# GPRS_0831.net
KiCad netlist of a schematic drawn in Altium Designer
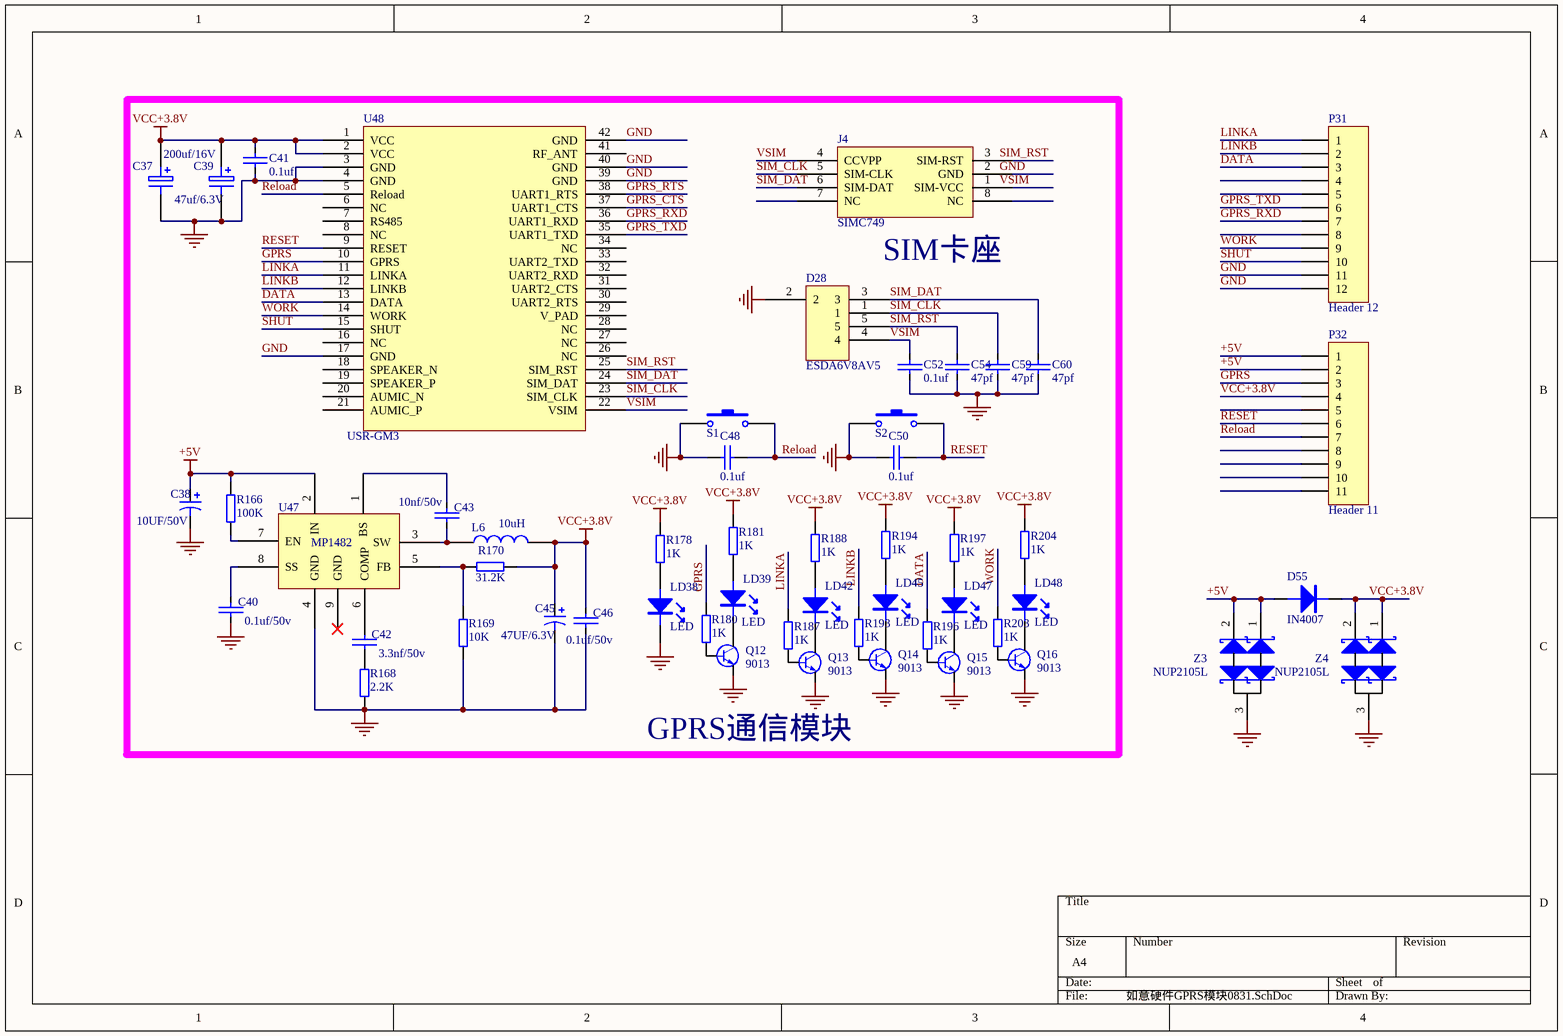
[diagram p0: 如意硬件GPRS模块0831.SchDoc]

(export (version "E")
  (design (tool "Eeschema 10.0.6"))
  (components
    (comp (ref "C37")
      (value "200uf/16V")
      (footprint "1206D-S")
      (description "Electrolytic Capacitor")
      (libsource (lib "*") (part "ELECTRO1"))
    )
    (comp (ref "C38")
      (value "10UF/50V")
      (footprint "1206D-S")
      (description "Polarized Capacitor (Radial)")
      (fields (field (name "Comment") "Cap Pol1") (field (name "PUBLISHER") "Altium Limited"))
      (libsource (lib "Miscellaneous Devices") (part "Cap Pol1"))
    )
    (comp (ref "C39")
      (value "47uf/6.3V")
      (footprint "1206D-S")
      (description "Electrolytic Capacitor")
      (libsource (lib "*") (part "ELECTRO1"))
    )
    (comp (ref "C40") (value "0.1uf/50v") (footprint "0603C-1") (libsource (lib "*") (part "C")))
    (comp (ref "C41") (value "0.1uf") (footprint "0603C-1") (libsource (lib "*") (part "C")))
    (comp (ref "C42") (value "3.3nf/50v") (footprint "0603C-1") (libsource (lib "*") (part "C")))
    (comp (ref "C43") (value "10nf/50v") (footprint "1206D-S") (libsource (lib "*") (part "C")))
    (comp (ref "C45")
      (value "47UF/6.3V")
      (footprint "1206D-S")
      (description "Polarized Capacitor (Radial)")
      (fields (field (name "Comment") "Cap Pol1") (field (name "PUBLISHER") "Altium Limited"))
      (libsource (lib "Miscellaneous Devices") (part "Cap Pol1"))
    )
    (comp (ref "C46") (value "0.1uf/50v") (footprint "0603C-1") (libsource (lib "*") (part "C")))
    (comp (ref "C48")
      (value "0.1uf")
      (footprint "0603C-1")
      (description "Capacitor")
      (libsource (lib "*") (part "CAP"))
    )
    (comp (ref "C50")
      (value "0.1uf")
      (footprint "0603C-1")
      (description "Capacitor")
      (libsource (lib "*") (part "CAP"))
    )
    (comp (ref "C52") (value "0.1uf") (footprint "0603C-1") (libsource (lib "*") (part "C")))
    (comp (ref "C54") (value "47pf") (footprint "0603C-1") (libsource (lib "*") (part "C")))
    (comp (ref "C59") (value "47pf") (footprint "0603C-1") (libsource (lib "*") (part "C")))
    (comp (ref "C60") (value "47pf") (footprint "0603C-1") (libsource (lib "*") (part "C")))
    (comp (ref "D28")
      (value "ESDA6V8AV5")
      (footprint "SOT-553")
      (libsource (lib "zongruyi") (part "ESDA6V8AV5"))
    )
    (comp (ref "D55")
      (value "IN4007")
      (footprint "DIODETP-5")
      (description "Diode")
      (libsource (lib "*") (part "DIODE"))
    )
    (comp (ref "J4") (value "SIMC749") (footprint "SIMPUSH") (libsource (lib "zongruyi") (part "SIMC749")))
    (comp (ref "L6") (value "10uH") (footprint "NR8030") (libsource (lib "*") (part "INDUCTOR")))
    (comp (ref "LD38") (value "LED") (footprint "LED_Z1") (libsource (lib "*") (part "LED")))
    (comp (ref "LD39") (value "LED") (footprint "LED_Z1") (libsource (lib "*") (part "LED")))
    (comp (ref "LD42") (value "LED") (footprint "LED_Z1") (libsource (lib "*") (part "LED")))
    (comp (ref "LD45") (value "LED") (footprint "LED_Z1") (libsource (lib "*") (part "LED")))
    (comp (ref "LD47") (value "LED") (footprint "LED_Z1") (libsource (lib "*") (part "LED")))
    (comp (ref "LD48") (value "LED") (footprint "LED_Z1") (libsource (lib "*") (part "LED")))
    (comp (ref "P31")
      (value "Header 12")
      (footprint "HDR1X12")
      (description "Header, 12-Pin")
      (fields (field (name "PUBLISHER") "Altium Limited"))
      (libsource (lib "Miscellaneous Connectors") (part "Header 12"))
    )
    (comp (ref "P32")
      (value "Header 11")
      (footprint "HDR1X11")
      (description "Header, 11-Pin")
      (fields (field (name "PUBLISHER") "Altium Limited"))
      (libsource (lib "Miscellaneous Connectors") (part "Header 11"))
    )
    (comp (ref "Q12") (value "9013") (footprint "SOT23-BCE") (libsource (lib "*") (part "NPN")))
    (comp (ref "Q13") (value "9013") (footprint "SOT23-BCE") (libsource (lib "*") (part "NPN")))
    (comp (ref "Q14") (value "9013") (footprint "SOT23-BCE") (libsource (lib "*") (part "NPN")))
    (comp (ref "Q15") (value "9013") (footprint "SOT23-BCE") (libsource (lib "*") (part "NPN")))
    (comp (ref "Q16") (value "9013") (footprint "SOT23-BCE") (libsource (lib "*") (part "NPN")))
    (comp (ref "R166") (value "100K") (footprint "0603R-1") (libsource (lib "") (part "RES-2_1")))
    (comp (ref "R168") (value "2.2K") (footprint "0603R-1") (libsource (lib "") (part "RES-2_1")))
    (comp (ref "R169") (value "10K") (footprint "0603R-1") (libsource (lib "") (part "RES-2_1")))
    (comp (ref "R170") (value "31.2K") (footprint "0603R-1") (libsource (lib "") (part "RES-2_1")))
    (comp (ref "R178") (value "1K") (footprint "0603R-1") (libsource (lib "*") (part "RES-2")))
    (comp (ref "R180") (value "1K") (footprint "0603R-1") (libsource (lib "*") (part "RES-2")))
    (comp (ref "R181") (value "1K") (footprint "0603R-1") (libsource (lib "*") (part "RES-2")))
    (comp (ref "R187") (value "1K") (footprint "0603R-1") (libsource (lib "*") (part "RES-2")))
    (comp (ref "R188") (value "1K") (footprint "0603R-1") (libsource (lib "*") (part "RES-2")))
    (comp (ref "R193") (value "1K") (footprint "0603R-1") (libsource (lib "*") (part "RES-2")))
    (comp (ref "R194") (value "1K") (footprint "0603R-1") (libsource (lib "*") (part "RES-2")))
    (comp (ref "R196") (value "1K") (footprint "0603R-1") (libsource (lib "*") (part "RES-2")))
    (comp (ref "R197") (value "1K") (footprint "0603R-1") (libsource (lib "*") (part "RES-2")))
    (comp (ref "R203") (value "1K") (footprint "0603R-1") (libsource (lib "*") (part "RES-2")))
    (comp (ref "R204") (value "1K") (footprint "0603R-1") (libsource (lib "*") (part "RES-2")))
    (comp (ref "S1")
      (value "SW-PB")
      (footprint "SW_PB4_A1")
      (description "Switch")
      (fields (field (name "PUBLISHER") "Altium Limited"))
      (libsource (lib "*") (part "SW-PB"))
    )
    (comp (ref "S2")
      (value "SW-PB")
      (footprint "SW_PB4_A1")
      (description "Switch")
      (fields (field (name "PUBLISHER") "Altium Limited"))
      (libsource (lib "*") (part "SW-PB"))
    )
    (comp (ref "U47") (value "MP1482") (footprint "SO-8") (libsource (lib "zongruyi") (part "MP1482")))
    (comp (ref "U48") (value "USR-GM3") (footprint "USR-GM3") (libsource (lib "zongruyi") (part "USR-GM3")))
    (comp (ref "Z3")
      (value "NUP2105L")
      (footprint "SOT-23")
      (description "过压保护")
      (libsource (lib "Fszhang") (part "PESD1CAN"))
    )
    (comp (ref "Z4")
      (value "NUP2105L")
      (footprint "SOT-23")
      (description "过压保护")
      (libsource (lib "Fszhang") (part "PESD1CAN"))
    )
  )
  (nets
    (net (code "1") (name "+5V") (class "Default")
      (node (ref "C38") (pin "1") (pinfunction "1_1") (pintype "passive"))
      (node (ref "D55") (pin "1") (pinfunction "A_1") (pintype "passive"))
      (node (ref "P32") (pin "1") (pinfunction "1_1") (pintype "passive"))
      (node (ref "P32") (pin "2") (pinfunction "2_2") (pintype "passive"))
      (node (ref "R166") (pin "1") (pinfunction "1_1") (pintype "passive"))
      (node (ref "U47") (pin "2") (pinfunction "IN_2") (pintype "passive"))
      (node (ref "Z3") (pin "1") (pintype "passive"))
      (node (ref "Z3") (pin "2") (pintype "passive"))
    )
    (net (code "2") (name "/DATA") (class "Default")
      (node (ref "P31") (pin "3") (pinfunction "3_3") (pintype "passive"))
      (node (ref "R196") (pin "1") (pinfunction "1_1") (pintype "passive"))
      (node (ref "U48") (pin "13") (pinfunction "DATA_13") (pintype "passive"))
    )
    (net (code "3") (name "/GPRS") (class "Default")
      (node (ref "P32") (pin "3") (pinfunction "3_3") (pintype "passive"))
      (node (ref "R180") (pin "1") (pinfunction "1_1") (pintype "passive"))
      (node (ref "U48") (pin "10") (pinfunction "GPRS_10") (pintype "passive"))
    )
    (net (code "4") (name "/GPRS_CTS") (class "Default")
      (node (ref "U48") (pin "37") (pinfunction "UART1_CTS_37") (pintype "passive"))
    )
    (net (code "5") (name "/GPRS_RTS") (class "Default")
      (node (ref "U48") (pin "38") (pinfunction "UART1_RTS_38") (pintype "passive"))
    )
    (net (code "6") (name "/GPRS_RXD") (class "Default")
      (node (ref "P31") (pin "7") (pinfunction "7_7") (pintype "passive"))
      (node (ref "U48") (pin "36") (pinfunction "UART1_RXD_36") (pintype "passive"))
    )
    (net (code "7") (name "/GPRS_TXD") (class "Default")
      (node (ref "P31") (pin "6") (pinfunction "6_6") (pintype "passive"))
      (node (ref "U48") (pin "35") (pinfunction "UART1_TXD_35") (pintype "passive"))
    )
    (net (code "8") (name "/LINKA") (class "Default")
      (node (ref "P31") (pin "1") (pinfunction "1_1") (pintype "passive"))
      (node (ref "R187") (pin "1") (pinfunction "1_1") (pintype "passive"))
      (node (ref "U48") (pin "11") (pinfunction "LINKA_11") (pintype "passive"))
    )
    (net (code "9") (name "/LINKB") (class "Default")
      (node (ref "P31") (pin "2") (pinfunction "2_2") (pintype "passive"))
      (node (ref "R193") (pin "1") (pinfunction "1_1") (pintype "passive"))
      (node (ref "U48") (pin "12") (pinfunction "LINKB_12") (pintype "passive"))
    )
    (net (code "10") (name "/RESET") (class "Default")
      (node (ref "C50") (pin "1") (pinfunction "1_1") (pintype "passive"))
      (node (ref "P32") (pin "6") (pinfunction "6_6") (pintype "passive"))
      (node (ref "S2") (pin "2") (pinfunction "2_2") (pintype "passive"))
      (node (ref "U48") (pin "9") (pinfunction "RESET_9") (pintype "passive"))
    )
    (net (code "11") (name "/Reload") (class "Default")
      (node (ref "C48") (pin "1") (pinfunction "1_1") (pintype "passive"))
      (node (ref "P32") (pin "7") (pinfunction "7_7") (pintype "passive"))
      (node (ref "S1") (pin "2") (pinfunction "2_2") (pintype "passive"))
      (node (ref "U48") (pin "5") (pinfunction "Reload_5") (pintype "passive"))
    )
    (net (code "12") (name "/SHUT") (class "Default")
      (node (ref "P31") (pin "10") (pinfunction "10_10") (pintype "passive"))
      (node (ref "U48") (pin "15") (pinfunction "SHUT_15") (pintype "passive"))
    )
    (net (code "13") (name "/SIM_CLK") (class "Default")
      (node (ref "C59") (pin "1") (pinfunction "1_1") (pintype "passive"))
      (node (ref "D28") (pin "1") (pinfunction "1_1") (pintype "passive"))
      (node (ref "J4") (pin "5") (pinfunction "SIM-CLK_5") (pintype "passive"))
      (node (ref "U48") (pin "23") (pinfunction "SIM_CLK_23") (pintype "passive"))
    )
    (net (code "14") (name "/SIM_DAT") (class "Default")
      (node (ref "C60") (pin "1") (pinfunction "1_1") (pintype "passive"))
      (node (ref "D28") (pin "3") (pinfunction "3_3") (pintype "passive"))
      (node (ref "J4") (pin "6") (pinfunction "SIM-DAT_6") (pintype "passive"))
      (node (ref "U48") (pin "24") (pinfunction "SIM_DAT_24") (pintype "passive"))
    )
    (net (code "15") (name "/SIM_RST") (class "Default")
      (node (ref "C54") (pin "1") (pinfunction "1_1") (pintype "passive"))
      (node (ref "D28") (pin "5") (pinfunction "5_5") (pintype "passive"))
      (node (ref "U48") (pin "25") (pinfunction "SIM_RST_25") (pintype "passive"))
    )
    (net (code "16") (name "/VSIM") (class "Default")
      (node (ref "C52") (pin "1") (pinfunction "1_1") (pintype "passive"))
      (node (ref "D28") (pin "4") (pinfunction "4_4") (pintype "passive"))
      (node (ref "J4") (pin "4") (pinfunction "CCVPP_4") (pintype "passive"))
      (node (ref "U48") (pin "22") (pinfunction "VSIM_22") (pintype "passive"))
    )
    (net (code "17") (name "/WORK") (class "Default")
      (node (ref "P31") (pin "9") (pinfunction "9_9") (pintype "passive"))
      (node (ref "R203") (pin "1") (pinfunction "1_1") (pintype "passive"))
      (node (ref "U48") (pin "14") (pinfunction "WORK_14") (pintype "passive"))
    )
    (net (code "18") (name "GND") (class "Default")
      (node (ref "C37") (pin "2") (pinfunction "2_2") (pintype "passive"))
      (node (ref "C38") (pin "2") (pinfunction "2_2") (pintype "passive"))
      (node (ref "C39") (pin "2") (pinfunction "2_2") (pintype "passive"))
      (node (ref "C40") (pin "2") (pinfunction "2_2") (pintype "passive"))
      (node (ref "C41") (pin "2") (pinfunction "2_2") (pintype "passive"))
      (node (ref "C45") (pin "2") (pinfunction "2_2") (pintype "passive"))
      (node (ref "C46") (pin "2") (pinfunction "2_2") (pintype "passive"))
      (node (ref "C48") (pin "2") (pinfunction "2_2") (pintype "passive"))
      (node (ref "C50") (pin "2") (pinfunction "2_2") (pintype "passive"))
      (node (ref "C52") (pin "2") (pinfunction "2_2") (pintype "passive"))
      (node (ref "C54") (pin "2") (pinfunction "2_2") (pintype "passive"))
      (node (ref "C59") (pin "2") (pinfunction "2_2") (pintype "passive"))
      (node (ref "C60") (pin "2") (pinfunction "2_2") (pintype "passive"))
      (node (ref "D28") (pin "2") (pinfunction "2_2") (pintype "passive"))
      (node (ref "LD38") (pin "2") (pinfunction "2_2") (pintype "passive"))
      (node (ref "P31") (pin "11") (pinfunction "11_11") (pintype "passive"))
      (node (ref "P31") (pin "12") (pinfunction "12_12") (pintype "passive"))
      (node (ref "Q12") (pin "E") (pintype "passive"))
      (node (ref "Q13") (pin "E") (pintype "passive"))
      (node (ref "Q14") (pin "E") (pintype "passive"))
      (node (ref "Q15") (pin "E") (pintype "passive"))
      (node (ref "Q16") (pin "E") (pintype "passive"))
      (node (ref "R168") (pin "2") (pinfunction "2_2") (pintype "passive"))
      (node (ref "R169") (pin "2") (pinfunction "2_2") (pintype "passive"))
      (node (ref "S1") (pin "1") (pinfunction "1_1") (pintype "passive"))
      (node (ref "S2") (pin "1") (pinfunction "1_1") (pintype "passive"))
      (node (ref "U47") (pin "4") (pinfunction "GND_4") (pintype "passive"))
      (node (ref "U48") (pin "17") (pinfunction "GND_17") (pintype "passive"))
      (node (ref "U48") (pin "3") (pinfunction "GND_3") (pintype "passive"))
      (node (ref "U48") (pin "39") (pinfunction "GND_39") (pintype "passive"))
      (node (ref "U48") (pin "4") (pinfunction "GND_4") (pintype "passive"))
      (node (ref "U48") (pin "40") (pinfunction "GND_40") (pintype "passive"))
      (node (ref "U48") (pin "42") (pinfunction "GND_42") (pintype "passive"))
      (node (ref "Z3") (pin "3") (pintype "passive"))
      (node (ref "Z4") (pin "3") (pintype "passive"))
    )
    (net (code "19") (name "Net-(C42-Pad2)") (class "Default")
      (node (ref "C42") (pin "2") (pinfunction "2_2") (pintype "passive"))
      (node (ref "R168") (pin "1") (pinfunction "1_1") (pintype "passive"))
    )
    (net (code "20") (name "Net-(LD38-Pad1)") (class "Default")
      (node (ref "LD38") (pin "1") (pinfunction "1_1") (pintype "passive"))
      (node (ref "R178") (pin "2") (pinfunction "2_2") (pintype "passive"))
    )
    (net (code "21") (name "Net-(LD39-Pad1)") (class "Default")
      (node (ref "LD39") (pin "1") (pinfunction "1_1") (pintype "passive"))
      (node (ref "R181") (pin "2") (pinfunction "2_2") (pintype "passive"))
    )
    (net (code "22") (name "Net-(LD39-Pad2)") (class "Default")
      (node (ref "LD39") (pin "2") (pinfunction "2_2") (pintype "passive"))
      (node (ref "Q12") (pin "C") (pintype "passive"))
    )
    (net (code "23") (name "Net-(LD42-Pad1)") (class "Default")
      (node (ref "LD42") (pin "1") (pinfunction "1_1") (pintype "passive"))
      (node (ref "R188") (pin "2") (pinfunction "2_2") (pintype "passive"))
    )
    (net (code "24") (name "Net-(LD42-Pad2)") (class "Default")
      (node (ref "LD42") (pin "2") (pinfunction "2_2") (pintype "passive"))
      (node (ref "Q13") (pin "C") (pintype "passive"))
    )
    (net (code "25") (name "Net-(LD45-Pad1)") (class "Default")
      (node (ref "LD45") (pin "1") (pinfunction "1_1") (pintype "passive"))
      (node (ref "R194") (pin "2") (pinfunction "2_2") (pintype "passive"))
    )
    (net (code "26") (name "Net-(LD45-Pad2)") (class "Default")
      (node (ref "LD45") (pin "2") (pinfunction "2_2") (pintype "passive"))
      (node (ref "Q14") (pin "C") (pintype "passive"))
    )
    (net (code "27") (name "Net-(LD47-Pad1)") (class "Default")
      (node (ref "LD47") (pin "1") (pinfunction "1_1") (pintype "passive"))
      (node (ref "R197") (pin "2") (pinfunction "2_2") (pintype "passive"))
    )
    (net (code "28") (name "Net-(LD47-Pad2)") (class "Default")
      (node (ref "LD47") (pin "2") (pinfunction "2_2") (pintype "passive"))
      (node (ref "Q15") (pin "C") (pintype "passive"))
    )
    (net (code "29") (name "Net-(LD48-Pad1)") (class "Default")
      (node (ref "LD48") (pin "1") (pinfunction "1_1") (pintype "passive"))
      (node (ref "R204") (pin "2") (pinfunction "2_2") (pintype "passive"))
    )
    (net (code "30") (name "Net-(LD48-Pad2)") (class "Default")
      (node (ref "LD48") (pin "2") (pinfunction "2_2") (pintype "passive"))
      (node (ref "Q16") (pin "C") (pintype "passive"))
    )
    (net (code "31") (name "Net-(Q12-PadB)") (class "Default")
      (node (ref "Q12") (pin "B") (pintype "passive"))
      (node (ref "R180") (pin "2") (pinfunction "2_2") (pintype "passive"))
    )
    (net (code "32") (name "Net-(Q13-PadB)") (class "Default")
      (node (ref "Q13") (pin "B") (pintype "passive"))
      (node (ref "R187") (pin "2") (pinfunction "2_2") (pintype "passive"))
    )
    (net (code "33") (name "Net-(Q14-PadB)") (class "Default")
      (node (ref "Q14") (pin "B") (pintype "passive"))
      (node (ref "R193") (pin "2") (pinfunction "2_2") (pintype "passive"))
    )
    (net (code "34") (name "Net-(Q15-PadB)") (class "Default")
      (node (ref "Q15") (pin "B") (pintype "passive"))
      (node (ref "R196") (pin "2") (pinfunction "2_2") (pintype "passive"))
    )
    (net (code "35") (name "Net-(Q16-PadB)") (class "Default")
      (node (ref "Q16") (pin "B") (pintype "passive"))
      (node (ref "R203") (pin "2") (pinfunction "2_2") (pintype "passive"))
    )
    (net (code "36") (name "Net-(U47-BS)") (class "Default")
      (node (ref "C43") (pin "1") (pinfunction "1_1") (pintype "passive"))
      (node (ref "U47") (pin "1") (pinfunction "BS_1") (pintype "passive"))
    )
    (net (code "37") (name "Net-(U47-COMP)") (class "Default")
      (node (ref "C42") (pin "1") (pinfunction "1_1") (pintype "passive"))
      (node (ref "U47") (pin "6") (pinfunction "COMP_6") (pintype "passive"))
    )
    (net (code "38") (name "Net-(U47-EN)") (class "Default")
      (node (ref "R166") (pin "2") (pinfunction "2_2") (pintype "passive"))
      (node (ref "U47") (pin "7") (pinfunction "EN_7") (pintype "passive"))
    )
    (net (code "39") (name "Net-(U47-FB)") (class "Default")
      (node (ref "R169") (pin "1") (pinfunction "1_1") (pintype "passive"))
      (node (ref "R170") (pin "1") (pinfunction "1_1") (pintype "passive"))
      (node (ref "U47") (pin "5") (pinfunction "FB_5") (pintype "passive"))
    )
    (net (code "40") (name "Net-(U47-SS)") (class "Default")
      (node (ref "C40") (pin "1") (pinfunction "1_1") (pintype "passive"))
      (node (ref "U47") (pin "8") (pinfunction "SS_8") (pintype "passive"))
    )
    (net (code "41") (name "Net-(U47-SW)") (class "Default")
      (node (ref "C43") (pin "2") (pinfunction "2_2") (pintype "passive"))
      (node (ref "L6") (pin "1") (pinfunction "1_1") (pintype "passive"))
      (node (ref "U47") (pin "3") (pinfunction "SW_3") (pintype "passive"))
    )
    (net (code "42") (name "VCC+3.8V") (class "Default")
      (node (ref "C37") (pin "1") (pinfunction "1_1") (pintype "passive"))
      (node (ref "C39") (pin "1") (pinfunction "1_1") (pintype "passive"))
      (node (ref "C41") (pin "1") (pinfunction "1_1") (pintype "passive"))
      (node (ref "C45") (pin "1") (pinfunction "1_1") (pintype "passive"))
      (node (ref "C46") (pin "1") (pinfunction "1_1") (pintype "passive"))
      (node (ref "D55") (pin "2") (pinfunction "K_2") (pintype "passive"))
      (node (ref "L6") (pin "2") (pinfunction "2_2") (pintype "passive"))
      (node (ref "P32") (pin "4") (pinfunction "4_4") (pintype "passive"))
      (node (ref "R170") (pin "2") (pinfunction "2_2") (pintype "passive"))
      (node (ref "R178") (pin "1") (pinfunction "1_1") (pintype "passive"))
      (node (ref "R181") (pin "1") (pinfunction "1_1") (pintype "passive"))
      (node (ref "R188") (pin "1") (pinfunction "1_1") (pintype "passive"))
      (node (ref "R194") (pin "1") (pinfunction "1_1") (pintype "passive"))
      (node (ref "R197") (pin "1") (pinfunction "1_1") (pintype "passive"))
      (node (ref "R204") (pin "1") (pinfunction "1_1") (pintype "passive"))
      (node (ref "U48") (pin "1") (pinfunction "VCC_1") (pintype "passive"))
      (node (ref "U48") (pin "2") (pinfunction "VCC_2") (pintype "passive"))
      (node (ref "Z4") (pin "1") (pintype "passive"))
      (node (ref "Z4") (pin "2") (pintype "passive"))
    )
    (net (code "43") (name "unconnected-(J4-GND-Pad2)") (class "Default")
      (node (ref "J4") (pin "2") (pinfunction "GND_2") (pintype "passive"))
    )
    (net (code "44") (name "unconnected-(J4-NC-Pad7)") (class "Default")
      (node (ref "J4") (pin "7") (pinfunction "NC_7") (pintype "passive"))
    )
    (net (code "45") (name "unconnected-(J4-NC-Pad8)") (class "Default")
      (node (ref "J4") (pin "8") (pinfunction "NC_8") (pintype "passive"))
    )
    (net (code "46") (name "unconnected-(J4-SIM-RST-Pad3)") (class "Default")
      (node (ref "J4") (pin "3") (pinfunction "SIM-RST_3") (pintype "passive"))
    )
    (net (code "47") (name "unconnected-(J4-SIM-VCC-Pad1)") (class "Default")
      (node (ref "J4") (pin "1") (pinfunction "SIM-VCC_1") (pintype "passive"))
    )
    (net (code "48") (name "unconnected-(P31-Pad4)") (class "Default")
      (node (ref "P31") (pin "4") (pinfunction "4_4") (pintype "passive"))
    )
    (net (code "49") (name "unconnected-(P31-Pad5)") (class "Default")
      (node (ref "P31") (pin "5") (pinfunction "5_5") (pintype "passive"))
    )
    (net (code "50") (name "unconnected-(P31-Pad8)") (class "Default")
      (node (ref "P31") (pin "8") (pinfunction "8_8") (pintype "passive"))
    )
    (net (code "51") (name "unconnected-(P32-Pad5)") (class "Default")
      (node (ref "P32") (pin "5") (pinfunction "5_5") (pintype "passive"))
    )
    (net (code "52") (name "unconnected-(P32-Pad8)") (class "Default")
      (node (ref "P32") (pin "8") (pinfunction "8_8") (pintype "passive"))
    )
    (net (code "53") (name "unconnected-(P32-Pad9)") (class "Default")
      (node (ref "P32") (pin "9") (pinfunction "9_9") (pintype "passive"))
    )
    (net (code "54") (name "unconnected-(P32-Pad10)") (class "Default")
      (node (ref "P32") (pin "10") (pinfunction "10_10") (pintype "passive"))
    )
    (net (code "55") (name "unconnected-(P32-Pad11)") (class "Default")
      (node (ref "P32") (pin "11") (pinfunction "11_11") (pintype "passive"))
    )
    (net (code "56") (name "unconnected-(U47-GND-Pad9)") (class "Default")
      (node (ref "U47") (pin "9") (pinfunction "GND_9") (pintype "passive+no_connect"))
    )
    (net (code "57") (name "unconnected-(U48-AUMIC_N-Pad20)") (class "Default")
      (node (ref "U48") (pin "20") (pinfunction "AUMIC_N_20") (pintype "passive"))
    )
    (net (code "58") (name "unconnected-(U48-AUMIC_P-Pad21)") (class "Default")
      (node (ref "U48") (pin "21") (pinfunction "AUMIC_P_21") (pintype "passive"))
    )
    (net (code "59") (name "unconnected-(U48-NC-Pad6)") (class "Default")
      (node (ref "U48") (pin "6") (pinfunction "NC_6") (pintype "passive"))
    )
    (net (code "60") (name "unconnected-(U48-NC-Pad8)") (class "Default")
      (node (ref "U48") (pin "8") (pinfunction "NC_8") (pintype "passive"))
    )
    (net (code "61") (name "unconnected-(U48-NC-Pad16)") (class "Default")
      (node (ref "U48") (pin "16") (pinfunction "NC_16") (pintype "passive"))
    )
    (net (code "62") (name "unconnected-(U48-NC-Pad26)") (class "Default")
      (node (ref "U48") (pin "26") (pinfunction "NC_26") (pintype "passive"))
    )
    (net (code "63") (name "unconnected-(U48-NC-Pad27)") (class "Default")
      (node (ref "U48") (pin "27") (pinfunction "NC_27") (pintype "passive"))
    )
    (net (code "64") (name "unconnected-(U48-NC-Pad28)") (class "Default")
      (node (ref "U48") (pin "28") (pinfunction "NC_28") (pintype "passive"))
    )
    (net (code "65") (name "unconnected-(U48-NC-Pad34)") (class "Default")
      (node (ref "U48") (pin "34") (pinfunction "NC_34") (pintype "passive"))
    )
    (net (code "66") (name "unconnected-(U48-RF_ANT-Pad41)") (class "Default")
      (node (ref "U48") (pin "41") (pinfunction "RF_ANT_41") (pintype "passive"))
    )
    (net (code "67") (name "unconnected-(U48-RS485-Pad7)") (class "Default")
      (node (ref "U48") (pin "7") (pinfunction "RS485_7") (pintype "passive"))
    )
    (net (code "68") (name "unconnected-(U48-SPEAKER_N-Pad18)") (class "Default")
      (node (ref "U48") (pin "18") (pinfunction "SPEAKER_N_18") (pintype "passive"))
    )
    (net (code "69") (name "unconnected-(U48-SPEAKER_P-Pad19)") (class "Default")
      (node (ref "U48") (pin "19") (pinfunction "SPEAKER_P_19") (pintype "passive"))
    )
    (net (code "70") (name "unconnected-(U48-UART2_CTS-Pad31)") (class "Default")
      (node (ref "U48") (pin "31") (pinfunction "UART2_CTS_31") (pintype "passive"))
    )
    (net (code "71") (name "unconnected-(U48-UART2_RTS-Pad30)") (class "Default")
      (node (ref "U48") (pin "30") (pinfunction "UART2_RTS_30") (pintype "passive"))
    )
    (net (code "72") (name "unconnected-(U48-UART2_RXD-Pad32)") (class "Default")
      (node (ref "U48") (pin "32") (pinfunction "UART2_RXD_32") (pintype "passive"))
    )
    (net (code "73") (name "unconnected-(U48-UART2_TXD-Pad33)") (class "Default")
      (node (ref "U48") (pin "33") (pinfunction "UART2_TXD_33") (pintype "passive"))
    )
    (net (code "74") (name "unconnected-(U48-V_PAD-Pad29)") (class "Default")
      (node (ref "U48") (pin "29") (pinfunction "V_PAD_29") (pintype "passive"))
    )
  )
)
